# Power.net
KiCad netlist of a schematic drawn in Altium Designer
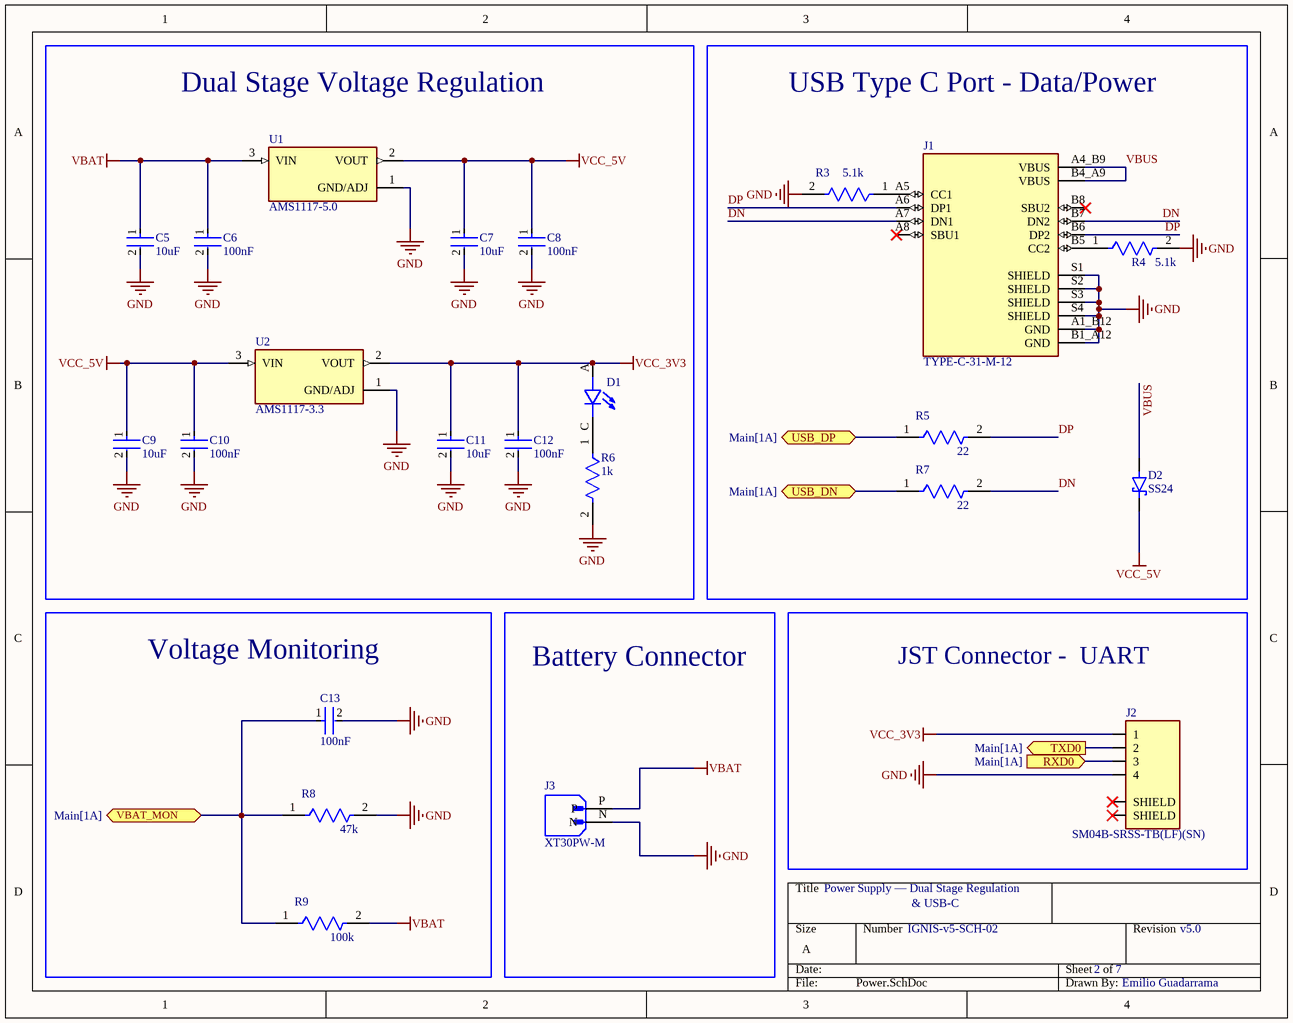
[diagram p0: Power.SchDoc]

(export (version "E")
  (design (tool "Eeschema 10.0.6"))
  (components
    (comp (ref "C5")
      (value "10uF")
      (footprint "FP-C0805C-DN-MFG")
      (description "CAP CER 0.1UF 50V X7R 0805")
      (fields
        (field (name "MANUFACTURER PART NUMBER") "C0805C104K5RACTU")
        (field (name "MANUFACTURER") "KEMET")
      )
      (libsource (lib "Altium Content Vault") (part "b4654b650e69147ec39a6b967a45e02"))
    )
    (comp (ref "C6")
      (value "100nF")
      (footprint "FP-C0805C-DN-MFG")
      (description "CAP CER 0.1UF 50V X7R 0805")
      (fields
        (field (name "MANUFACTURER PART NUMBER") "C0805C104K5RACTU")
        (field (name "MANUFACTURER") "KEMET")
      )
      (libsource (lib "Altium Content Vault") (part "b4654b650e69147ec39a6b967a45e02"))
    )
    (comp (ref "C7")
      (value "10uF")
      (footprint "FP-C0805C-DN-MFG")
      (description "CAP CER 0.1UF 50V X7R 0805")
      (fields
        (field (name "MANUFACTURER PART NUMBER") "C0805C104K5RACTU")
        (field (name "MANUFACTURER") "KEMET")
      )
      (libsource (lib "Altium Content Vault") (part "b4654b650e69147ec39a6b967a45e02"))
    )
    (comp (ref "C8")
      (value "100nF")
      (footprint "FP-C0805C-DN-MFG")
      (description "CAP CER 0.1UF 50V X7R 0805")
      (fields
        (field (name "MANUFACTURER PART NUMBER") "C0805C104K5RACTU")
        (field (name "MANUFACTURER") "KEMET")
      )
      (libsource (lib "Altium Content Vault") (part "b4654b650e69147ec39a6b967a45e02"))
    )
    (comp (ref "C9")
      (value "10uF")
      (footprint "FP-C0805C-DN-MFG")
      (description "CAP CER 0.1UF 50V X7R 0805")
      (fields
        (field (name "MANUFACTURER PART NUMBER") "C0805C104K5RACTU")
        (field (name "MANUFACTURER") "KEMET")
      )
      (libsource (lib "Altium Content Vault") (part "b4654b650e69147ec39a6b967a45e02"))
    )
    (comp (ref "C10")
      (value "100nF")
      (footprint "FP-C0805C-DN-MFG")
      (description "CAP CER 0.1UF 50V X7R 0805")
      (fields
        (field (name "MANUFACTURER PART NUMBER") "C0805C104K5RACTU")
        (field (name "MANUFACTURER") "KEMET")
      )
      (libsource (lib "Altium Content Vault") (part "b4654b650e69147ec39a6b967a45e02"))
    )
    (comp (ref "C11")
      (value "10uF")
      (footprint "FP-C0805C-DN-MFG")
      (description "CAP CER 0.1UF 50V X7R 0805")
      (fields
        (field (name "MANUFACTURER PART NUMBER") "C0805C104K5RACTU")
        (field (name "MANUFACTURER") "KEMET")
      )
      (libsource (lib "Altium Content Vault") (part "b4654b650e69147ec39a6b967a45e02"))
    )
    (comp (ref "C12")
      (value "100nF")
      (footprint "FP-C0805C-DN-MFG")
      (description "CAP CER 0.1UF 50V X7R 0805")
      (fields
        (field (name "MANUFACTURER PART NUMBER") "C0805C104K5RACTU")
        (field (name "MANUFACTURER") "KEMET")
      )
      (libsource (lib "Altium Content Vault") (part "b4654b650e69147ec39a6b967a45e02"))
    )
    (comp (ref "C13")
      (value "100nF")
      (footprint "FP-C0805C-DN-MFG")
      (description "CAP CER 0.1UF 50V X7R 0805")
      (fields
        (field (name "MANUFACTURER PART NUMBER") "C0805C104K5RACTU")
        (field (name "MANUFACTURER") "KEMET")
      )
      (libsource (lib "Altium Content Vault") (part "b4654b650e69147ec39a6b967a45e02"))
    )
    (comp (ref "D1")
      (value "SML-LXT0805IW-TR")
      (footprint "LEDC2012X120N")
      (fields (field (name "MF") "Lumex Opto/Components"))
      (libsource (lib "LED_0805-SML-LXT0805IW-TR") (part "SML-LXT0805IW-TR"))
    )
    (comp (ref "D2")
      (value "SS24")
      (footprint "DIOM4336X265N")
      (description "2A, 40V, Schottky Rectifier")
      (fields (field (name "MF") "Taiwan Semiconductor"))
      (libsource (lib "SS24") (part "SS24"))
    )
    (comp (ref "J1")
      (value "TYPE-C-31-M-12")
      (footprint "HRO_TYPE-C-31-M-12")
      (description "USB Connectors 24 Receptacle 1 8.94*7.3mm RoHS")
      (fields (field (name "MF") "HRO Electronics Co., Ltd."))
      (libsource (lib "TYPE-C-31-M-12") (part "TYPE-C-31-M-12"))
    )
    (comp (ref "J2")
      (value "SM04B-SRSS-TB(LF)(SN)")
      (footprint "JST_SM04B-SRSS-TB(LF)(SN)")
      (description "Connector Header Surface Mount, Right Angle 4 position 0.039 (1.00mm)")
      (fields (field (name "MF") "JST Sales"))
      (libsource (lib "SM04B-SRSS-TB_LF__SN_") (part "SM04B-SRSS-TB(LF)(SN)"))
    )
    (comp (ref "J3")
      (value "XT30PW-M")
      (footprint "AMASS_XT30PW-M")
      (description "Socket; DC supply; XT30; male; PIN: 2; on PCBs; THT; Colour: yellow")
      (fields (field (name "MF") "AMASS"))
      (libsource (lib "XT30PW-M") (part "XT30PW-M"))
    )
    (comp (ref "R3")
      (value "5.1k")
      (footprint "FP-MCT0603-IPC_A")
      (description "RES SMD 100 OHM 1% 1/8W 0603")
      (fields (field (name "TOLERANCE") "0.1%"))
      (libsource (lib "Altium Content Vault") (part "1029c3af85768c4190bb7ad29bc67b5"))
    )
    (comp (ref "R4")
      (value "5.1k")
      (footprint "FP-MCT0603-IPC_A")
      (description "RES SMD 100 OHM 1% 1/8W 0603")
      (fields (field (name "TOLERANCE") "0.1%"))
      (libsource (lib "Altium Content Vault") (part "1029c3af85768c4190bb7ad29bc67b5"))
    )
    (comp (ref "R5")
      (value "22")
      (footprint "FP-MCT0603-IPC_A")
      (description "RES SMD 100 OHM 1% 1/8W 0603")
      (fields (field (name "TOLERANCE") "0.1%"))
      (libsource (lib "Altium Content Vault") (part "1029c3af85768c4190bb7ad29bc67b5"))
    )
    (comp (ref "R6")
      (value "1k")
      (footprint "FP-MCT0603-IPC_A")
      (description "RES SMD 100 OHM 1% 1/8W 0603")
      (fields (field (name "TOLERANCE") "0.1%"))
      (libsource (lib "Altium Content Vault") (part "1029c3af85768c4190bb7ad29bc67b5"))
    )
    (comp (ref "R7")
      (value "22")
      (footprint "FP-MCT0603-IPC_A")
      (description "RES SMD 100 OHM 1% 1/8W 0603")
      (fields (field (name "TOLERANCE") "0.1%"))
      (libsource (lib "Altium Content Vault") (part "1029c3af85768c4190bb7ad29bc67b5"))
    )
    (comp (ref "R8")
      (value "47k")
      (footprint "FP-MCT0603-IPC_A")
      (description "RES SMD 100 OHM 1% 1/8W 0603")
      (fields (field (name "TOLERANCE") "0.1%"))
      (libsource (lib "Altium Content Vault") (part "1029c3af85768c4190bb7ad29bc67b5"))
    )
    (comp (ref "R9")
      (value "100k")
      (footprint "FP-MCT0603-IPC_A")
      (description "RES SMD 100 OHM 1% 1/8W 0603")
      (fields (field (name "TOLERANCE") "0.1%"))
      (libsource (lib "Altium Content Vault") (part "1029c3af85768c4190bb7ad29bc67b5"))
    )
    (comp (ref "U1")
      (value "AMS1117-5.0")
      (footprint "SOT229P700X180-4N")
      (description "1A LOW DROPOUT VOLTAGE REGULATOR")
      (fields (field (name "MF") "ams"))
      (libsource (lib "AMS1117-3v3") (part "AMS1117-5.0"))
    )
    (comp (ref "U2")
      (value "AMS1117-3.3")
      (footprint "SOT229P700X180-4N")
      (description "1A LOW DROPOUT VOLTAGE REGULATOR")
      (fields (field (name "MP") "AMS1117-5.0") (field (name "MF") "ams"))
      (libsource (lib "AMS1117-3v3") (part "AMS1117-5.0"))
    )
  )
  (nets
    (net (code "1") (name "/DN") (class "Default")
      (node (ref "J1") (pin "A7") (pinfunction "DN1_A7") (pintype "bidirectional"))
      (node (ref "J1") (pin "B7") (pinfunction "DN2_B7") (pintype "bidirectional"))
      (node (ref "R7") (pin "2") (pinfunction "2_2") (pintype "passive"))
    )
    (net (code "2") (name "/DP") (class "Default")
      (node (ref "J1") (pin "A6") (pinfunction "DP1_A6") (pintype "bidirectional"))
      (node (ref "J1") (pin "B6") (pinfunction "DP2_B6") (pintype "bidirectional"))
      (node (ref "R5") (pin "2") (pinfunction "2_2") (pintype "passive"))
    )
    (net (code "3") (name "/RXD0") (class "Default")
      (node (ref "J2") (pin "3") (pinfunction "3_3") (pintype "passive"))
    )
    (net (code "4") (name "/TXD0") (class "Default")
      (node (ref "J2") (pin "2") (pinfunction "2_2") (pintype "passive"))
    )
    (net (code "5") (name "/USB_DN") (class "Default")
      (node (ref "R7") (pin "1") (pinfunction "1_1") (pintype "passive"))
    )
    (net (code "6") (name "/USB_DP") (class "Default")
      (node (ref "R5") (pin "1") (pinfunction "1_1") (pintype "passive"))
    )
    (net (code "7") (name "/VBAT_MON") (class "Default")
      (node (ref "C13") (pin "1") (pinfunction "1_1") (pintype "passive"))
      (node (ref "R8") (pin "1") (pinfunction "1_1") (pintype "passive"))
      (node (ref "R9") (pin "1") (pinfunction "1_1") (pintype "passive"))
    )
    (net (code "8") (name "/VBUS") (class "Default")
      (node (ref "D2") (pin "A") (pinfunction "A_A") (pintype "passive"))
      (node (ref "J1") (pin "A4_B9") (pinfunction "VBUS_A4_B9") (pintype "power_in"))
      (node (ref "J1") (pin "B4_A9") (pinfunction "VBUS_B4_A9") (pintype "power_in"))
    )
    (net (code "9") (name "GND") (class "Default")
      (node (ref "C10") (pin "2") (pinfunction "2_2") (pintype "passive"))
      (node (ref "C11") (pin "2") (pinfunction "2_2") (pintype "passive"))
      (node (ref "C12") (pin "2") (pinfunction "2_2") (pintype "passive"))
      (node (ref "C13") (pin "2") (pinfunction "2_2") (pintype "passive"))
      (node (ref "C5") (pin "2") (pinfunction "2_2") (pintype "passive"))
      (node (ref "C6") (pin "2") (pinfunction "2_2") (pintype "passive"))
      (node (ref "C7") (pin "2") (pinfunction "2_2") (pintype "passive"))
      (node (ref "C8") (pin "2") (pinfunction "2_2") (pintype "passive"))
      (node (ref "C9") (pin "2") (pinfunction "2_2") (pintype "passive"))
      (node (ref "J1") (pin "A1_B12") (pinfunction "GND_A1_B12") (pintype "power_in"))
      (node (ref "J1") (pin "B1_A12") (pinfunction "GND_B1_A12") (pintype "power_in"))
      (node (ref "J1") (pin "S1") (pinfunction "SHIELD_S1") (pintype "passive"))
      (node (ref "J1") (pin "S2") (pinfunction "SHIELD_S2") (pintype "passive"))
      (node (ref "J1") (pin "S3") (pinfunction "SHIELD_S3") (pintype "passive"))
      (node (ref "J1") (pin "S4") (pinfunction "SHIELD_S4") (pintype "passive"))
      (node (ref "J2") (pin "4") (pinfunction "4_4") (pintype "passive"))
      (node (ref "J3") (pin "N") (pinfunction "N_N") (pintype "power_in"))
      (node (ref "R3") (pin "2") (pinfunction "2_2") (pintype "passive"))
      (node (ref "R4") (pin "2") (pinfunction "2_2") (pintype "passive"))
      (node (ref "R6") (pin "2") (pinfunction "2_2") (pintype "passive"))
      (node (ref "R8") (pin "2") (pinfunction "2_2") (pintype "passive"))
      (node (ref "U1") (pin "1") (pinfunction "GND/ADJ_1") (pintype "power_in"))
      (node (ref "U2") (pin "1") (pinfunction "GND/ADJ_1") (pintype "power_in"))
    )
    (net (code "10") (name "Net-(D1-PadC)") (class "Default")
      (node (ref "D1") (pin "C") (pinfunction "C_C") (pintype "passive"))
      (node (ref "R6") (pin "1") (pinfunction "1_1") (pintype "passive"))
    )
    (net (code "11") (name "Net-(J1-CC1)") (class "Default")
      (node (ref "J1") (pin "A5") (pinfunction "CC1_A5") (pintype "bidirectional"))
      (node (ref "R3") (pin "1") (pinfunction "1_1") (pintype "passive"))
    )
    (net (code "12") (name "Net-(J1-CC2)") (class "Default")
      (node (ref "J1") (pin "B5") (pinfunction "CC2_B5") (pintype "bidirectional"))
      (node (ref "R4") (pin "1") (pinfunction "1_1") (pintype "passive"))
    )
    (net (code "13") (name "VBAT") (class "Default")
      (node (ref "C5") (pin "1") (pinfunction "1_1") (pintype "passive"))
      (node (ref "C6") (pin "1") (pinfunction "1_1") (pintype "passive"))
      (node (ref "J3") (pin "P") (pinfunction "P_P") (pintype "power_in"))
      (node (ref "R9") (pin "2") (pinfunction "2_2") (pintype "passive"))
      (node (ref "U1") (pin "3") (pinfunction "VIN_3") (pintype "input"))
    )
    (net (code "14") (name "VCC_3V3") (class "Default")
      (node (ref "C11") (pin "1") (pinfunction "1_1") (pintype "passive"))
      (node (ref "C12") (pin "1") (pinfunction "1_1") (pintype "passive"))
      (node (ref "D1") (pin "A") (pinfunction "A_A") (pintype "passive"))
      (node (ref "J2") (pin "1") (pinfunction "1_1") (pintype "passive"))
      (node (ref "U2") (pin "2") (pinfunction "VOUT_2") (pintype "output"))
    )
    (net (code "15") (name "VCC_5V") (class "Default")
      (node (ref "C10") (pin "1") (pinfunction "1_1") (pintype "passive"))
      (node (ref "C7") (pin "1") (pinfunction "1_1") (pintype "passive"))
      (node (ref "C8") (pin "1") (pinfunction "1_1") (pintype "passive"))
      (node (ref "C9") (pin "1") (pinfunction "1_1") (pintype "passive"))
      (node (ref "D2") (pin "C") (pinfunction "K_C") (pintype "passive"))
      (node (ref "U1") (pin "2") (pinfunction "VOUT_2") (pintype "output"))
      (node (ref "U2") (pin "3") (pinfunction "VIN_3") (pintype "input"))
    )
    (net (code "16") (name "unconnected-(J1-SBU1-PadA8)") (class "Default")
      (node (ref "J1") (pin "A8") (pinfunction "SBU1_A8") (pintype "bidirectional+no_connect"))
    )
    (net (code "17") (name "unconnected-(J1-SBU2-PadB8)") (class "Default")
      (node (ref "J1") (pin "B8") (pinfunction "SBU2_B8") (pintype "bidirectional+no_connect"))
    )
    (net (code "18") (name "unconnected-(J2-SHIELD-PadS1)") (class "Default")
      (node (ref "J2") (pin "S1") (pinfunction "SHIELD_S1") (pintype "passive+no_connect"))
    )
    (net (code "19") (name "unconnected-(J2-SHIELD-PadS2)") (class "Default")
      (node (ref "J2") (pin "S2") (pinfunction "SHIELD_S2") (pintype "passive+no_connect"))
    )
  )
)
